# GlowDriver.net
KiCad netlist of a schematic drawn in EAGLE
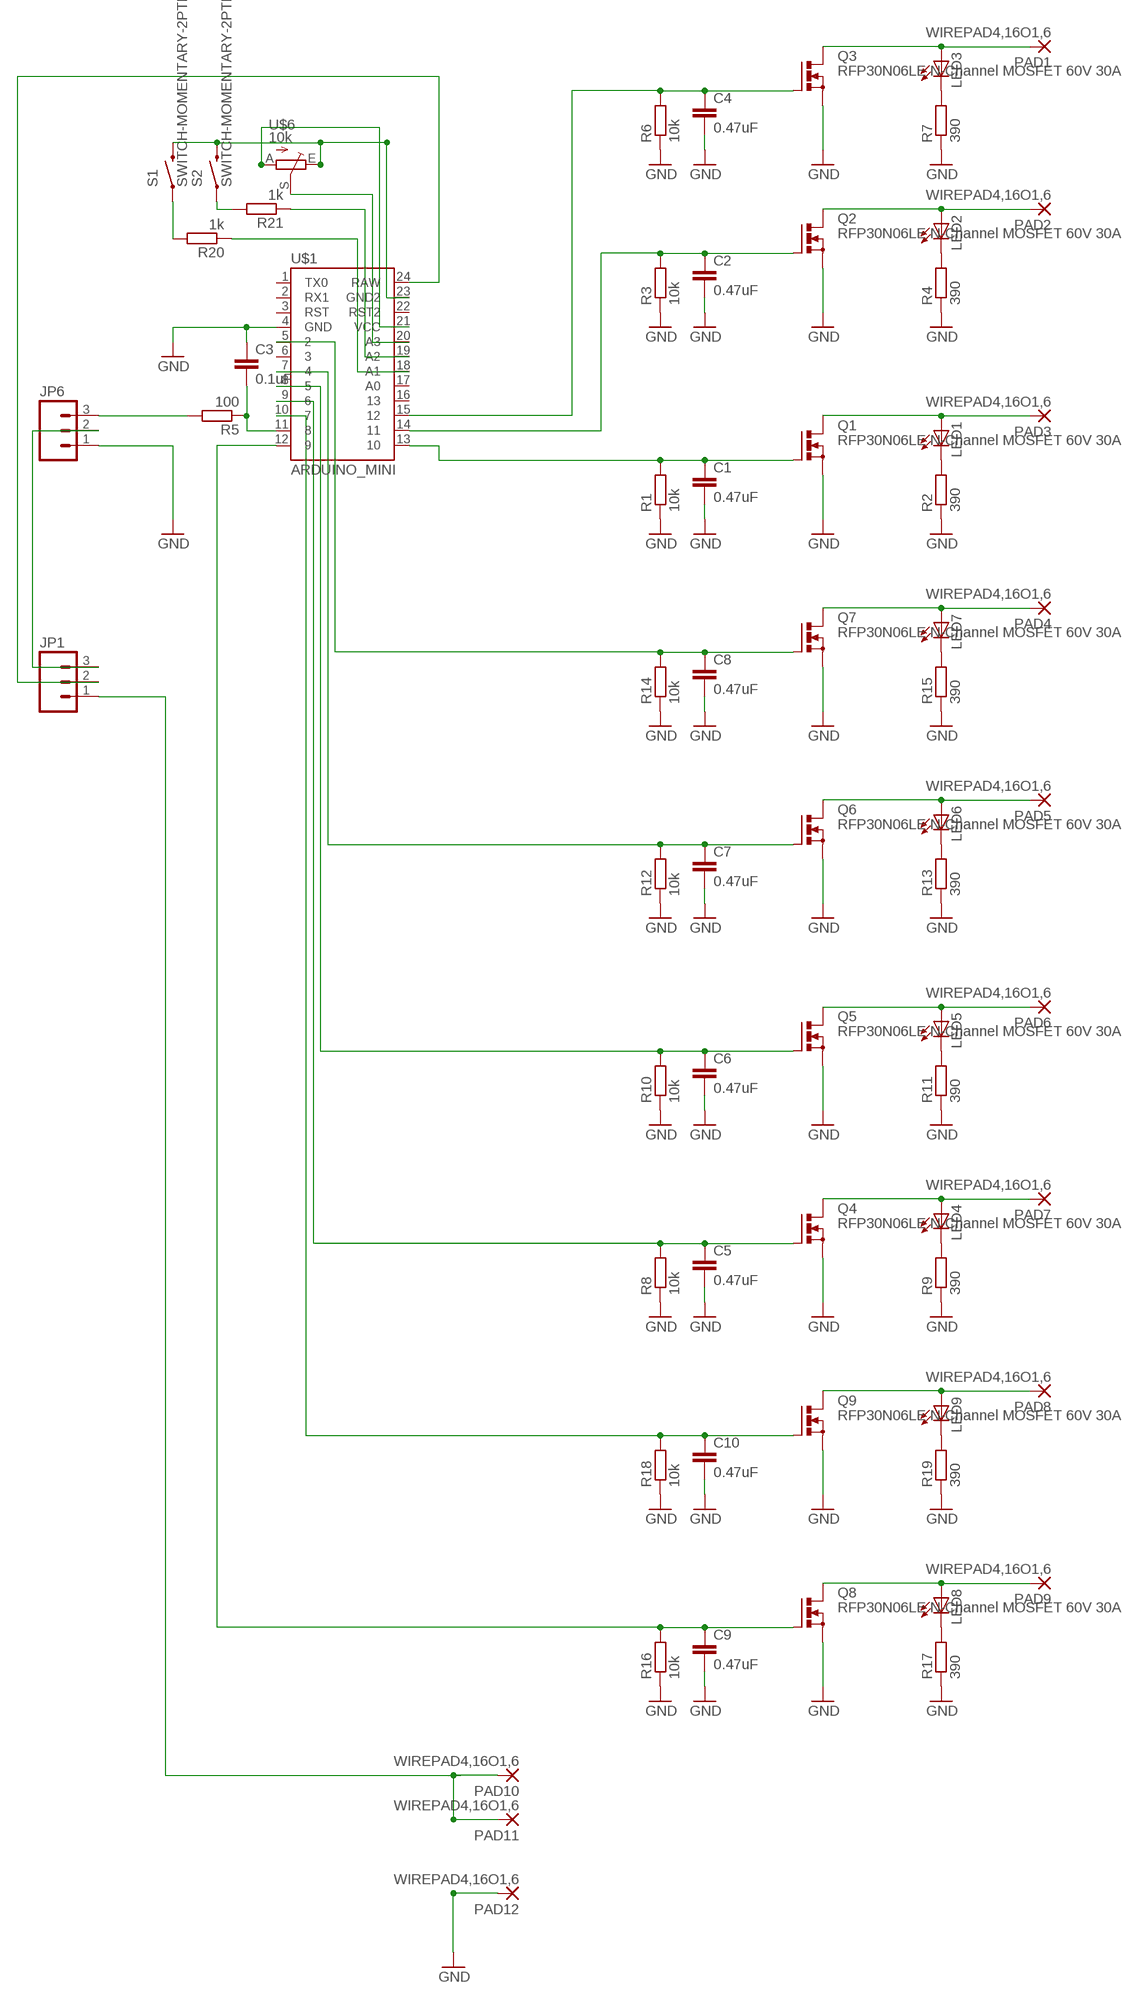
[diagram p0: schematic, sheet 1]

(export (version "E")
  (design (tool "Eeschema 10.0.6"))
  (components
    (comp (ref "C1")
      (value "0.47uF")
      (footprint "eagle-import:CAP-PTH-SMALLEZ")
      (libsource (lib "eagle-import") (part "CAPEZ"))
    )
    (comp (ref "C2")
      (value "0.47uF")
      (footprint "eagle-import:CAP-PTH-SMALLEZ")
      (libsource (lib "eagle-import") (part "CAPEZ"))
    )
    (comp (ref "C3")
      (value "0.1uF")
      (footprint "eagle-import:C050-035X075")
      (libsource (lib "eagle-import") (part "C-EU050-035X075"))
    )
    (comp (ref "C4")
      (value "0.47uF")
      (footprint "eagle-import:CAP-PTH-SMALLEZ")
      (libsource (lib "eagle-import") (part "CAPEZ"))
    )
    (comp (ref "C5")
      (value "0.47uF")
      (footprint "eagle-import:CAP-PTH-SMALLEZ")
      (libsource (lib "eagle-import") (part "CAPEZ"))
    )
    (comp (ref "C6")
      (value "0.47uF")
      (footprint "eagle-import:CAP-PTH-SMALLEZ")
      (libsource (lib "eagle-import") (part "CAPEZ"))
    )
    (comp (ref "C7")
      (value "0.47uF")
      (footprint "eagle-import:CAP-PTH-SMALLEZ")
      (libsource (lib "eagle-import") (part "CAPEZ"))
    )
    (comp (ref "C8")
      (value "0.47uF")
      (footprint "eagle-import:CAP-PTH-SMALLEZ")
      (libsource (lib "eagle-import") (part "CAPEZ"))
    )
    (comp (ref "C9")
      (value "0.47uF")
      (footprint "eagle-import:CAP-PTH-SMALLEZ")
      (libsource (lib "eagle-import") (part "CAPEZ"))
    )
    (comp (ref "C10")
      (value "0.47uF")
      (footprint "eagle-import:CAP-PTH-SMALLEZ")
      (libsource (lib "eagle-import") (part "CAPEZ"))
    )
    (comp (ref "JP1")
      (value "M03PTH")
      (footprint "eagle-import:1X03")
      (libsource (lib "eagle-import") (part "M03PTH"))
    )
    (comp (ref "JP6")
      (value "M03PTH")
      (footprint "eagle-import:1X03")
      (libsource (lib "eagle-import") (part "M03PTH"))
    )
    (comp (ref "LED1")
      (value "LED5MM")
      (footprint "eagle-import:LED5MM")
      (libsource (lib "eagle-import") (part "LED5MM"))
    )
    (comp (ref "LED2")
      (value "LED5MM")
      (footprint "eagle-import:LED5MM")
      (libsource (lib "eagle-import") (part "LED5MM"))
    )
    (comp (ref "LED3")
      (value "LED5MM")
      (footprint "eagle-import:LED5MM")
      (libsource (lib "eagle-import") (part "LED5MM"))
    )
    (comp (ref "LED4")
      (value "LED5MM")
      (footprint "eagle-import:LED5MM")
      (libsource (lib "eagle-import") (part "LED5MM"))
    )
    (comp (ref "LED5")
      (value "LED5MM")
      (footprint "eagle-import:LED5MM")
      (libsource (lib "eagle-import") (part "LED5MM"))
    )
    (comp (ref "LED6")
      (value "LED5MM")
      (footprint "eagle-import:LED5MM")
      (libsource (lib "eagle-import") (part "LED5MM"))
    )
    (comp (ref "LED7")
      (value "LED5MM")
      (footprint "eagle-import:LED5MM")
      (libsource (lib "eagle-import") (part "LED5MM"))
    )
    (comp (ref "LED8")
      (value "LED5MM")
      (footprint "eagle-import:LED5MM")
      (libsource (lib "eagle-import") (part "LED5MM"))
    )
    (comp (ref "LED9")
      (value "LED5MM")
      (footprint "eagle-import:LED5MM")
      (libsource (lib "eagle-import") (part "LED5MM"))
    )
    (comp (ref "PAD1")
      (value "WIREPAD4,16O1,6")
      (footprint "eagle-import:4,16O1,6")
      (libsource (lib "eagle-import") (part "WIREPAD4,16O1,6"))
    )
    (comp (ref "PAD2")
      (value "WIREPAD4,16O1,6")
      (footprint "eagle-import:4,16O1,6")
      (libsource (lib "eagle-import") (part "WIREPAD4,16O1,6"))
    )
    (comp (ref "PAD3")
      (value "WIREPAD4,16O1,6")
      (footprint "eagle-import:4,16O1,6")
      (libsource (lib "eagle-import") (part "WIREPAD4,16O1,6"))
    )
    (comp (ref "PAD4")
      (value "WIREPAD4,16O1,6")
      (footprint "eagle-import:4,16O1,6")
      (libsource (lib "eagle-import") (part "WIREPAD4,16O1,6"))
    )
    (comp (ref "PAD5")
      (value "WIREPAD4,16O1,6")
      (footprint "eagle-import:4,16O1,6")
      (libsource (lib "eagle-import") (part "WIREPAD4,16O1,6"))
    )
    (comp (ref "PAD6")
      (value "WIREPAD4,16O1,6")
      (footprint "eagle-import:4,16O1,6")
      (libsource (lib "eagle-import") (part "WIREPAD4,16O1,6"))
    )
    (comp (ref "PAD7")
      (value "WIREPAD4,16O1,6")
      (footprint "eagle-import:4,16O1,6")
      (libsource (lib "eagle-import") (part "WIREPAD4,16O1,6"))
    )
    (comp (ref "PAD8")
      (value "WIREPAD4,16O1,6")
      (footprint "eagle-import:4,16O1,6")
      (libsource (lib "eagle-import") (part "WIREPAD4,16O1,6"))
    )
    (comp (ref "PAD9")
      (value "WIREPAD4,16O1,6")
      (footprint "eagle-import:4,16O1,6")
      (libsource (lib "eagle-import") (part "WIREPAD4,16O1,6"))
    )
    (comp (ref "PAD10")
      (value "WIREPAD4,16O1,6")
      (footprint "eagle-import:4,16O1,6")
      (libsource (lib "eagle-import") (part "WIREPAD4,16O1,6"))
    )
    (comp (ref "PAD11")
      (value "WIREPAD4,16O1,6")
      (footprint "eagle-import:4,16O1,6")
      (libsource (lib "eagle-import") (part "WIREPAD4,16O1,6"))
    )
    (comp (ref "PAD12")
      (value "WIREPAD4,16O1,6")
      (footprint "eagle-import:4,16O1,6")
      (libsource (lib "eagle-import") (part "WIREPAD4,16O1,6"))
    )
    (comp (ref "Q1")
      (value "RFP30N06LE N-Channel MOSFET 60V 30A")
      (footprint "eagle-import:TO220BV")
      (libsource (lib "eagle-import") (part "PMOSFET_NTO220BV"))
    )
    (comp (ref "Q2")
      (value "RFP30N06LE N-Channel MOSFET 60V 30A")
      (footprint "eagle-import:TO220BV")
      (libsource (lib "eagle-import") (part "PMOSFET_NTO220BV"))
    )
    (comp (ref "Q3")
      (value "RFP30N06LE N-Channel MOSFET 60V 30A")
      (footprint "eagle-import:TO220BV")
      (libsource (lib "eagle-import") (part "PMOSFET_NTO220BV"))
    )
    (comp (ref "Q4")
      (value "RFP30N06LE N-Channel MOSFET 60V 30A")
      (footprint "eagle-import:TO220BV")
      (libsource (lib "eagle-import") (part "PMOSFET_NTO220BV"))
    )
    (comp (ref "Q5")
      (value "RFP30N06LE N-Channel MOSFET 60V 30A")
      (footprint "eagle-import:TO220BV")
      (libsource (lib "eagle-import") (part "PMOSFET_NTO220BV"))
    )
    (comp (ref "Q6")
      (value "RFP30N06LE N-Channel MOSFET 60V 30A")
      (footprint "eagle-import:TO220BV")
      (libsource (lib "eagle-import") (part "PMOSFET_NTO220BV"))
    )
    (comp (ref "Q7")
      (value "RFP30N06LE N-Channel MOSFET 60V 30A")
      (footprint "eagle-import:TO220BV")
      (libsource (lib "eagle-import") (part "PMOSFET_NTO220BV"))
    )
    (comp (ref "Q8")
      (value "RFP30N06LE N-Channel MOSFET 60V 30A")
      (footprint "eagle-import:TO220BV")
      (libsource (lib "eagle-import") (part "PMOSFET_NTO220BV"))
    )
    (comp (ref "Q9")
      (value "RFP30N06LE N-Channel MOSFET 60V 30A")
      (footprint "eagle-import:TO220BV")
      (libsource (lib "eagle-import") (part "PMOSFET_NTO220BV"))
    )
    (comp (ref "R1")
      (value "10k")
      (footprint "eagle-import:0207_2V")
      (libsource (lib "eagle-import") (part "R-EU_0207/2V"))
    )
    (comp (ref "R2")
      (value "390")
      (footprint "eagle-import:0207_2V")
      (libsource (lib "eagle-import") (part "R-EU_0207/2V"))
    )
    (comp (ref "R3")
      (value "10k")
      (footprint "eagle-import:0207_2V")
      (libsource (lib "eagle-import") (part "R-EU_0207/2V"))
    )
    (comp (ref "R4")
      (value "390")
      (footprint "eagle-import:0207_2V")
      (libsource (lib "eagle-import") (part "R-EU_0207/2V"))
    )
    (comp (ref "R5")
      (value "100")
      (footprint "eagle-import:0207_10")
      (libsource (lib "eagle-import") (part "R-EU_0207/10"))
    )
    (comp (ref "R6")
      (value "10k")
      (footprint "eagle-import:0207_2V")
      (libsource (lib "eagle-import") (part "R-EU_0207/2V"))
    )
    (comp (ref "R7")
      (value "390")
      (footprint "eagle-import:0207_2V")
      (libsource (lib "eagle-import") (part "R-EU_0207/2V"))
    )
    (comp (ref "R8")
      (value "10k")
      (footprint "eagle-import:0207_2V")
      (libsource (lib "eagle-import") (part "R-EU_0207/2V"))
    )
    (comp (ref "R9")
      (value "390")
      (footprint "eagle-import:0207_2V")
      (libsource (lib "eagle-import") (part "R-EU_0207/2V"))
    )
    (comp (ref "R10")
      (value "10k")
      (footprint "eagle-import:0207_2V")
      (libsource (lib "eagle-import") (part "R-EU_0207/2V"))
    )
    (comp (ref "R11")
      (value "390")
      (footprint "eagle-import:0207_2V")
      (libsource (lib "eagle-import") (part "R-EU_0207/2V"))
    )
    (comp (ref "R12")
      (value "10k")
      (footprint "eagle-import:0207_2V")
      (libsource (lib "eagle-import") (part "R-EU_0207/2V"))
    )
    (comp (ref "R13")
      (value "390")
      (footprint "eagle-import:0207_2V")
      (libsource (lib "eagle-import") (part "R-EU_0207/2V"))
    )
    (comp (ref "R14")
      (value "10k")
      (footprint "eagle-import:0207_2V")
      (libsource (lib "eagle-import") (part "R-EU_0207/2V"))
    )
    (comp (ref "R15")
      (value "390")
      (footprint "eagle-import:0207_2V")
      (libsource (lib "eagle-import") (part "R-EU_0207/2V"))
    )
    (comp (ref "R16")
      (value "10k")
      (footprint "eagle-import:0207_2V")
      (libsource (lib "eagle-import") (part "R-EU_0207/2V"))
    )
    (comp (ref "R17")
      (value "390")
      (footprint "eagle-import:0207_2V")
      (libsource (lib "eagle-import") (part "R-EU_0207/2V"))
    )
    (comp (ref "R18")
      (value "10k")
      (footprint "eagle-import:0207_2V")
      (libsource (lib "eagle-import") (part "R-EU_0207/2V"))
    )
    (comp (ref "R19")
      (value "390")
      (footprint "eagle-import:0207_2V")
      (libsource (lib "eagle-import") (part "R-EU_0207/2V"))
    )
    (comp (ref "R20")
      (value "1k")
      (footprint "eagle-import:0207_2V")
      (libsource (lib "eagle-import") (part "R-EU_0207/2V"))
    )
    (comp (ref "R21")
      (value "1k")
      (footprint "eagle-import:0207_2V")
      (libsource (lib "eagle-import") (part "R-EU_0207/2V"))
    )
    (comp (ref "S1")
      (value "SWITCH-MOMENTARY-2PTH")
      (footprint "eagle-import:TACTILE-PTH")
      (libsource (lib "eagle-import") (part "SWITCH-MOMENTARY-2PTH"))
    )
    (comp (ref "S2")
      (value "SWITCH-MOMENTARY-2PTH")
      (footprint "eagle-import:TACTILE-PTH")
      (libsource (lib "eagle-import") (part "SWITCH-MOMENTARY-2PTH"))
    )
    (comp (ref "U$1")
      (value "ARDUINO_MINI")
      (footprint "eagle-import:ARDUINO_MINI")
      (libsource (lib "eagle-import") (part "ARDUINO_MINI"))
    )
    (comp (ref "U$6")
      (value "10k")
      (footprint "eagle-import:PT-10")
      (libsource (lib "eagle-import") (part "TRIM_EU-PT10"))
    )
  )
  (nets
    (net (code "1") (name "GND") (class "Default")
      (node (ref "C1") (pin "2") (pinfunction "2_2") (pintype "passive"))
      (node (ref "C10") (pin "2") (pinfunction "2_2") (pintype "passive"))
      (node (ref "C2") (pin "2") (pinfunction "2_2") (pintype "passive"))
      (node (ref "C3") (pin "1") (pinfunction "1_1") (pintype "passive"))
      (node (ref "C4") (pin "2") (pinfunction "2_2") (pintype "passive"))
      (node (ref "C5") (pin "2") (pinfunction "2_2") (pintype "passive"))
      (node (ref "C6") (pin "2") (pinfunction "2_2") (pintype "passive"))
      (node (ref "C7") (pin "2") (pinfunction "2_2") (pintype "passive"))
      (node (ref "C8") (pin "2") (pinfunction "2_2") (pintype "passive"))
      (node (ref "C9") (pin "2") (pinfunction "2_2") (pintype "passive"))
      (node (ref "JP6") (pin "1") (pinfunction "1_1") (pintype "passive"))
      (node (ref "PAD12") (pin "1") (pinfunction "P_1") (pintype "passive"))
      (node (ref "Q1") (pin "S") (pinfunction "S_S") (pintype "passive"))
      (node (ref "Q2") (pin "S") (pinfunction "S_S") (pintype "passive"))
      (node (ref "Q3") (pin "S") (pinfunction "S_S") (pintype "passive"))
      (node (ref "Q4") (pin "S") (pinfunction "S_S") (pintype "passive"))
      (node (ref "Q5") (pin "S") (pinfunction "S_S") (pintype "passive"))
      (node (ref "Q6") (pin "S") (pinfunction "S_S") (pintype "passive"))
      (node (ref "Q7") (pin "S") (pinfunction "S_S") (pintype "passive"))
      (node (ref "Q8") (pin "S") (pinfunction "S_S") (pintype "passive"))
      (node (ref "Q9") (pin "S") (pinfunction "S_S") (pintype "passive"))
      (node (ref "R1") (pin "1") (pinfunction "1_1") (pintype "passive"))
      (node (ref "R10") (pin "1") (pinfunction "1_1") (pintype "passive"))
      (node (ref "R11") (pin "1") (pinfunction "1_1") (pintype "passive"))
      (node (ref "R12") (pin "1") (pinfunction "1_1") (pintype "passive"))
      (node (ref "R13") (pin "1") (pinfunction "1_1") (pintype "passive"))
      (node (ref "R14") (pin "1") (pinfunction "1_1") (pintype "passive"))
      (node (ref "R15") (pin "1") (pinfunction "1_1") (pintype "passive"))
      (node (ref "R16") (pin "1") (pinfunction "1_1") (pintype "passive"))
      (node (ref "R17") (pin "1") (pinfunction "1_1") (pintype "passive"))
      (node (ref "R18") (pin "1") (pinfunction "1_1") (pintype "passive"))
      (node (ref "R19") (pin "1") (pinfunction "1_1") (pintype "passive"))
      (node (ref "R2") (pin "1") (pinfunction "1_1") (pintype "passive"))
      (node (ref "R3") (pin "1") (pinfunction "1_1") (pintype "passive"))
      (node (ref "R4") (pin "1") (pinfunction "1_1") (pintype "passive"))
      (node (ref "R6") (pin "1") (pinfunction "1_1") (pintype "passive"))
      (node (ref "R7") (pin "1") (pinfunction "1_1") (pintype "passive"))
      (node (ref "R8") (pin "1") (pinfunction "1_1") (pintype "passive"))
      (node (ref "R9") (pin "1") (pinfunction "1_1") (pintype "passive"))
      (node (ref "U$1") (pin "4") (pinfunction "GND_4") (pintype "bidirectional"))
    )
    (net (code "2") (name "Net-(JP1-Pad3)") (class "Default")
      (node (ref "JP1") (pin "3") (pinfunction "3_3") (pintype "passive"))
      (node (ref "JP6") (pin "2") (pinfunction "2_2") (pintype "passive"))
    )
    (net (code "3") (name "Net-(JP6-Pad3)") (class "Default")
      (node (ref "JP6") (pin "3") (pinfunction "3_3") (pintype "passive"))
      (node (ref "R5") (pin "2") (pinfunction "2_2") (pintype "passive"))
    )
    (net (code "4") (name "Net-(LED1-C)") (class "Default")
      (node (ref "LED1") (pin "K") (pinfunction "C_K") (pintype "passive"))
      (node (ref "R2") (pin "2") (pinfunction "2_2") (pintype "passive"))
    )
    (net (code "5") (name "Net-(LED2-C)") (class "Default")
      (node (ref "LED2") (pin "K") (pinfunction "C_K") (pintype "passive"))
      (node (ref "R4") (pin "2") (pinfunction "2_2") (pintype "passive"))
    )
    (net (code "6") (name "Net-(LED3-C)") (class "Default")
      (node (ref "LED3") (pin "K") (pinfunction "C_K") (pintype "passive"))
      (node (ref "R7") (pin "2") (pinfunction "2_2") (pintype "passive"))
    )
    (net (code "7") (name "Net-(LED4-C)") (class "Default")
      (node (ref "LED4") (pin "K") (pinfunction "C_K") (pintype "passive"))
      (node (ref "R9") (pin "2") (pinfunction "2_2") (pintype "passive"))
    )
    (net (code "8") (name "Net-(LED5-C)") (class "Default")
      (node (ref "LED5") (pin "K") (pinfunction "C_K") (pintype "passive"))
      (node (ref "R11") (pin "2") (pinfunction "2_2") (pintype "passive"))
    )
    (net (code "9") (name "Net-(LED6-C)") (class "Default")
      (node (ref "LED6") (pin "K") (pinfunction "C_K") (pintype "passive"))
      (node (ref "R13") (pin "2") (pinfunction "2_2") (pintype "passive"))
    )
    (net (code "10") (name "Net-(LED7-C)") (class "Default")
      (node (ref "LED7") (pin "K") (pinfunction "C_K") (pintype "passive"))
      (node (ref "R15") (pin "2") (pinfunction "2_2") (pintype "passive"))
    )
    (net (code "11") (name "Net-(LED8-C)") (class "Default")
      (node (ref "LED8") (pin "K") (pinfunction "C_K") (pintype "passive"))
      (node (ref "R17") (pin "2") (pinfunction "2_2") (pintype "passive"))
    )
    (net (code "12") (name "Net-(LED9-C)") (class "Default")
      (node (ref "LED9") (pin "K") (pinfunction "C_K") (pintype "passive"))
      (node (ref "R19") (pin "2") (pinfunction "2_2") (pintype "passive"))
    )
    (net (code "13") (name "Net-(PAD1-P)") (class "Default")
      (node (ref "LED3") (pin "A") (pinfunction "A_A") (pintype "passive"))
      (node (ref "PAD1") (pin "1") (pinfunction "P_1") (pintype "passive"))
      (node (ref "Q3") (pin "D") (pinfunction "D_D") (pintype "passive"))
    )
    (net (code "14") (name "Net-(PAD2-P)") (class "Default")
      (node (ref "LED2") (pin "A") (pinfunction "A_A") (pintype "passive"))
      (node (ref "PAD2") (pin "1") (pinfunction "P_1") (pintype "passive"))
      (node (ref "Q2") (pin "D") (pinfunction "D_D") (pintype "passive"))
    )
    (net (code "15") (name "Net-(PAD3-P)") (class "Default")
      (node (ref "LED1") (pin "A") (pinfunction "A_A") (pintype "passive"))
      (node (ref "PAD3") (pin "1") (pinfunction "P_1") (pintype "passive"))
      (node (ref "Q1") (pin "D") (pinfunction "D_D") (pintype "passive"))
    )
    (net (code "16") (name "Net-(PAD4-P)") (class "Default")
      (node (ref "LED7") (pin "A") (pinfunction "A_A") (pintype "passive"))
      (node (ref "PAD4") (pin "1") (pinfunction "P_1") (pintype "passive"))
      (node (ref "Q7") (pin "D") (pinfunction "D_D") (pintype "passive"))
    )
    (net (code "17") (name "Net-(PAD5-P)") (class "Default")
      (node (ref "LED6") (pin "A") (pinfunction "A_A") (pintype "passive"))
      (node (ref "PAD5") (pin "1") (pinfunction "P_1") (pintype "passive"))
      (node (ref "Q6") (pin "D") (pinfunction "D_D") (pintype "passive"))
    )
    (net (code "18") (name "Net-(PAD6-P)") (class "Default")
      (node (ref "LED5") (pin "A") (pinfunction "A_A") (pintype "passive"))
      (node (ref "PAD6") (pin "1") (pinfunction "P_1") (pintype "passive"))
      (node (ref "Q5") (pin "D") (pinfunction "D_D") (pintype "passive"))
    )
    (net (code "19") (name "Net-(PAD7-P)") (class "Default")
      (node (ref "LED4") (pin "A") (pinfunction "A_A") (pintype "passive"))
      (node (ref "PAD7") (pin "1") (pinfunction "P_1") (pintype "passive"))
      (node (ref "Q4") (pin "D") (pinfunction "D_D") (pintype "passive"))
    )
    (net (code "20") (name "Net-(PAD8-P)") (class "Default")
      (node (ref "LED9") (pin "A") (pinfunction "A_A") (pintype "passive"))
      (node (ref "PAD8") (pin "1") (pinfunction "P_1") (pintype "passive"))
      (node (ref "Q9") (pin "D") (pinfunction "D_D") (pintype "passive"))
    )
    (net (code "21") (name "Net-(PAD9-P)") (class "Default")
      (node (ref "LED8") (pin "A") (pinfunction "A_A") (pintype "passive"))
      (node (ref "PAD9") (pin "1") (pinfunction "P_1") (pintype "passive"))
      (node (ref "Q8") (pin "D") (pinfunction "D_D") (pintype "passive"))
    )
    (net (code "22") (name "Net-(PAD10-P)") (class "Default")
      (node (ref "JP1") (pin "1") (pinfunction "1_1") (pintype "passive"))
      (node (ref "PAD10") (pin "1") (pinfunction "P_1") (pintype "passive"))
      (node (ref "PAD11") (pin "1") (pinfunction "P_1") (pintype "passive"))
    )
    (net (code "23") (name "Net-(R20-Pad2)") (class "Default")
      (node (ref "R20") (pin "2") (pinfunction "2_2") (pintype "passive"))
      (node (ref "S1") (pin "1") (pinfunction "1_1") (pintype "passive"))
    )
    (net (code "24") (name "Net-(R21-Pad2)") (class "Default")
      (node (ref "R21") (pin "2") (pinfunction "2_2") (pintype "passive"))
      (node (ref "S2") (pin "1") (pinfunction "1_1") (pintype "passive"))
    )
    (net (code "25") (name "Net-(S1-2)") (class "Default")
      (node (ref "S1") (pin "3") (pinfunction "2_3") (pintype "passive"))
      (node (ref "S2") (pin "3") (pinfunction "2_3") (pintype "passive"))
      (node (ref "U$1") (pin "23") (pinfunction "GND2_23") (pintype "bidirectional"))
      (node (ref "U$6") (pin "E") (pinfunction "E_E") (pintype "passive"))
    )
    (net (code "26") (name "Net-(U$1-2)") (class "Default")
      (node (ref "C8") (pin "1") (pinfunction "1_1") (pintype "passive"))
      (node (ref "Q7") (pin "G") (pinfunction "G_G") (pintype "passive"))
      (node (ref "R14") (pin "2") (pinfunction "2_2") (pintype "passive"))
      (node (ref "U$1") (pin "5") (pinfunction "2_5") (pintype "bidirectional"))
    )
    (net (code "27") (name "Net-(U$1-4)") (class "Default")
      (node (ref "C7") (pin "1") (pinfunction "1_1") (pintype "passive"))
      (node (ref "Q6") (pin "G") (pinfunction "G_G") (pintype "passive"))
      (node (ref "R12") (pin "2") (pinfunction "2_2") (pintype "passive"))
      (node (ref "U$1") (pin "7") (pinfunction "4_7") (pintype "bidirectional"))
    )
    (net (code "28") (name "Net-(U$1-5)") (class "Default")
      (node (ref "C6") (pin "1") (pinfunction "1_1") (pintype "passive"))
      (node (ref "Q5") (pin "G") (pinfunction "G_G") (pintype "passive"))
      (node (ref "R10") (pin "2") (pinfunction "2_2") (pintype "passive"))
      (node (ref "U$1") (pin "8") (pinfunction "5_8") (pintype "bidirectional"))
    )
    (net (code "29") (name "Net-(U$1-6)") (class "Default")
      (node (ref "C5") (pin "1") (pinfunction "1_1") (pintype "passive"))
      (node (ref "Q4") (pin "G") (pinfunction "G_G") (pintype "passive"))
      (node (ref "R8") (pin "2") (pinfunction "2_2") (pintype "passive"))
      (node (ref "U$1") (pin "9") (pinfunction "6_9") (pintype "bidirectional"))
    )
    (net (code "30") (name "Net-(U$1-7)") (class "Default")
      (node (ref "C10") (pin "1") (pinfunction "1_1") (pintype "passive"))
      (node (ref "Q9") (pin "G") (pinfunction "G_G") (pintype "passive"))
      (node (ref "R18") (pin "2") (pinfunction "2_2") (pintype "passive"))
      (node (ref "U$1") (pin "10") (pinfunction "7_10") (pintype "bidirectional"))
    )
    (net (code "31") (name "Net-(U$1-8)") (class "Default")
      (node (ref "C3") (pin "2") (pinfunction "2_2") (pintype "passive"))
      (node (ref "R5") (pin "1") (pinfunction "1_1") (pintype "passive"))
      (node (ref "U$1") (pin "11") (pinfunction "8_11") (pintype "bidirectional"))
    )
    (net (code "32") (name "Net-(U$1-9)") (class "Default")
      (node (ref "C9") (pin "1") (pinfunction "1_1") (pintype "passive"))
      (node (ref "Q8") (pin "G") (pinfunction "G_G") (pintype "passive"))
      (node (ref "R16") (pin "2") (pinfunction "2_2") (pintype "passive"))
      (node (ref "U$1") (pin "12") (pinfunction "9_12") (pintype "bidirectional"))
    )
    (net (code "33") (name "Net-(U$1-10)") (class "Default")
      (node (ref "C1") (pin "1") (pinfunction "1_1") (pintype "passive"))
      (node (ref "Q1") (pin "G") (pinfunction "G_G") (pintype "passive"))
      (node (ref "R1") (pin "2") (pinfunction "2_2") (pintype "passive"))
      (node (ref "U$1") (pin "13") (pinfunction "10_13") (pintype "bidirectional"))
    )
    (net (code "34") (name "Net-(U$1-11)") (class "Default")
      (node (ref "C2") (pin "1") (pinfunction "1_1") (pintype "passive"))
      (node (ref "Q2") (pin "G") (pinfunction "G_G") (pintype "passive"))
      (node (ref "R3") (pin "2") (pinfunction "2_2") (pintype "passive"))
      (node (ref "U$1") (pin "14") (pinfunction "11_14") (pintype "bidirectional"))
    )
    (net (code "35") (name "Net-(U$1-12)") (class "Default")
      (node (ref "C4") (pin "1") (pinfunction "1_1") (pintype "passive"))
      (node (ref "Q3") (pin "G") (pinfunction "G_G") (pintype "passive"))
      (node (ref "R6") (pin "2") (pinfunction "2_2") (pintype "passive"))
      (node (ref "U$1") (pin "15") (pinfunction "12_15") (pintype "bidirectional"))
    )
    (net (code "36") (name "Net-(U$1-A1)") (class "Default")
      (node (ref "R20") (pin "1") (pinfunction "1_1") (pintype "passive"))
      (node (ref "U$1") (pin "18") (pinfunction "A1_18") (pintype "bidirectional"))
    )
    (net (code "37") (name "Net-(U$1-A2)") (class "Default")
      (node (ref "R21") (pin "1") (pinfunction "1_1") (pintype "passive"))
      (node (ref "U$1") (pin "19") (pinfunction "A2_19") (pintype "bidirectional"))
    )
    (net (code "38") (name "Net-(U$1-A3)") (class "Default")
      (node (ref "U$1") (pin "20") (pinfunction "A3_20") (pintype "bidirectional"))
      (node (ref "U$6") (pin "S") (pinfunction "S_S") (pintype "passive"))
    )
    (net (code "39") (name "Net-(U$1-RAW)") (class "Default")
      (node (ref "JP1") (pin "2") (pinfunction "2_2") (pintype "passive"))
      (node (ref "U$1") (pin "24") (pinfunction "RAW_24") (pintype "bidirectional"))
    )
    (net (code "40") (name "Net-(U$1-VCC)") (class "Default")
      (node (ref "U$1") (pin "21") (pinfunction "VCC_21") (pintype "bidirectional"))
      (node (ref "U$6") (pin "A") (pinfunction "A_A") (pintype "passive"))
    )
    (net (code "41") (name "unconnected-(U$1-3-Pad6)") (class "Default")
      (node (ref "U$1") (pin "6") (pinfunction "3_6") (pintype "bidirectional"))
    )
    (net (code "42") (name "unconnected-(U$1-13-Pad16)") (class "Default")
      (node (ref "U$1") (pin "16") (pinfunction "13_16") (pintype "bidirectional"))
    )
    (net (code "43") (name "unconnected-(U$1-A0-Pad17)") (class "Default")
      (node (ref "U$1") (pin "17") (pinfunction "A0_17") (pintype "bidirectional"))
    )
    (net (code "44") (name "unconnected-(U$1-RST-Pad3)") (class "Default")
      (node (ref "U$1") (pin "3") (pinfunction "RST_3") (pintype "bidirectional"))
    )
    (net (code "45") (name "unconnected-(U$1-RST2-Pad22)") (class "Default")
      (node (ref "U$1") (pin "22") (pinfunction "RST2_22") (pintype "bidirectional"))
    )
    (net (code "46") (name "unconnected-(U$1-RX1-Pad2)") (class "Default")
      (node (ref "U$1") (pin "2") (pinfunction "RX1_2") (pintype "bidirectional"))
    )
    (net (code "47") (name "unconnected-(U$1-TX0-Pad1)") (class "Default")
      (node (ref "U$1") (pin "1") (pinfunction "TX0_1") (pintype "bidirectional"))
    )
  )
)
